# MOSEFET_CONTROLLER_V8.net
KiCad netlist of a schematic drawn in EAGLE
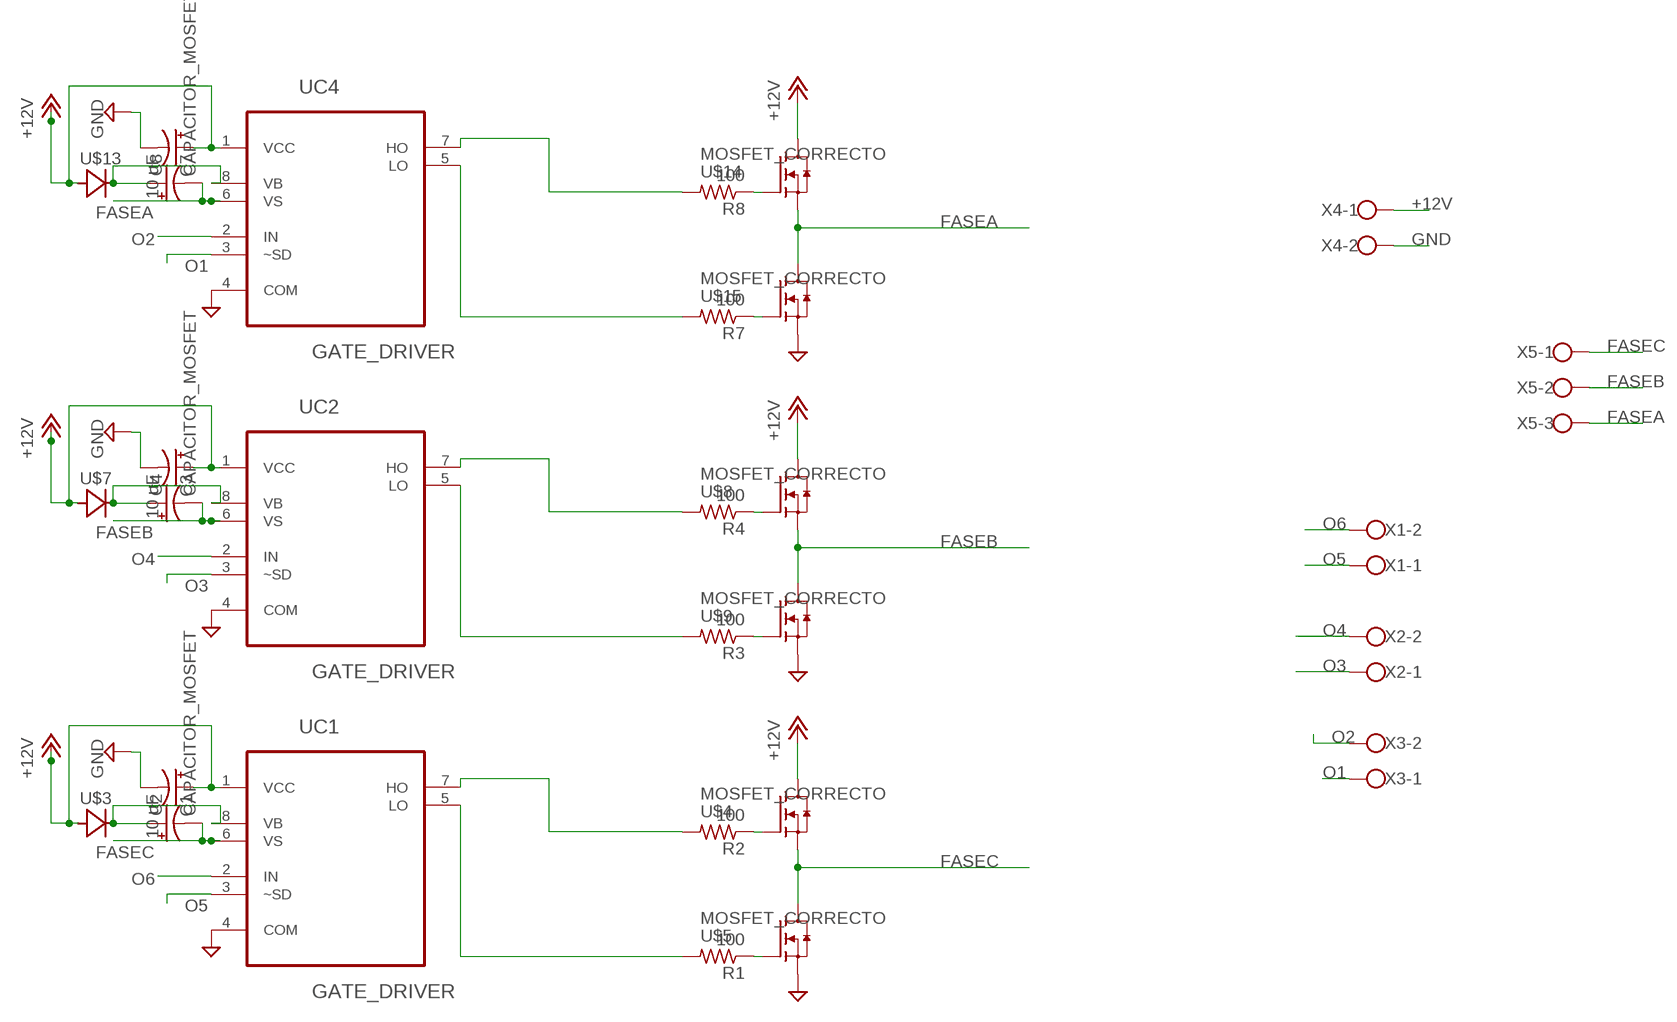
[diagram p0: schematic, sheet 1]

(export (version "E")
  (design (tool "Eeschema 10.0.6"))
  (components
    (comp (ref "C1")
      (value "10 uF")
      (footprint "eagle-import:153CLV-0505")
      (libsource (lib "eagle-import") (part "CAP_SMD"))
    )
    (comp (ref "C2")
      (value "CAPACITOR_MOSFET")
      (footprint "eagle-import:E2,5-5")
      (libsource (lib "eagle-import") (part "CAPACITOR_MOSFET"))
    )
    (comp (ref "C3")
      (value "10 uF")
      (footprint "eagle-import:153CLV-0505")
      (libsource (lib "eagle-import") (part "CAP_SMD"))
    )
    (comp (ref "C4")
      (value "CAPACITOR_MOSFET")
      (footprint "eagle-import:E2,5-5")
      (libsource (lib "eagle-import") (part "CAPACITOR_MOSFET"))
    )
    (comp (ref "C7")
      (value "10 uF")
      (footprint "eagle-import:153CLV-0505")
      (libsource (lib "eagle-import") (part "CAP_SMD"))
    )
    (comp (ref "C8")
      (value "CAPACITOR_MOSFET")
      (footprint "eagle-import:E2,5-5")
      (libsource (lib "eagle-import") (part "CAPACITOR_MOSFET"))
    )
    (comp (ref "R1")
      (value "100")
      (footprint "eagle-import:R1206")
      (libsource (lib "eagle-import") (part "R-US_R1206"))
    )
    (comp (ref "R2")
      (value "100")
      (footprint "eagle-import:R1206")
      (libsource (lib "eagle-import") (part "R-US_R1206"))
    )
    (comp (ref "R3")
      (value "100")
      (footprint "eagle-import:R1206")
      (libsource (lib "eagle-import") (part "R-US_R1206"))
    )
    (comp (ref "R4")
      (value "100")
      (footprint "eagle-import:R1206")
      (libsource (lib "eagle-import") (part "R-US_R1206"))
    )
    (comp (ref "R7")
      (value "100")
      (footprint "eagle-import:R1206")
      (libsource (lib "eagle-import") (part "R-US_R1206"))
    )
    (comp (ref "R8")
      (value "100")
      (footprint "eagle-import:R1206")
      (libsource (lib "eagle-import") (part "R-US_R1206"))
    )
    (comp (ref "U$3")
      (value "DIODO_SMD")
      (footprint "eagle-import:DO214AC")
      (libsource (lib "eagle-import") (part "DIODO_SMD"))
    )
    (comp (ref "U$4")
      (value "MOSFET_CORRECTO")
      (footprint "eagle-import:MOSFET_BUENO")
      (libsource (lib "eagle-import") (part "MOSFET_CORRECTO"))
    )
    (comp (ref "U$5")
      (value "MOSFET_CORRECTO")
      (footprint "eagle-import:MOSFET_BUENO")
      (libsource (lib "eagle-import") (part "MOSFET_CORRECTO"))
    )
    (comp (ref "U$7")
      (value "DIODO_SMD")
      (footprint "eagle-import:DO214AC")
      (libsource (lib "eagle-import") (part "DIODO_SMD"))
    )
    (comp (ref "U$8")
      (value "MOSFET_CORRECTO")
      (footprint "eagle-import:MOSFET_BUENO")
      (libsource (lib "eagle-import") (part "MOSFET_CORRECTO"))
    )
    (comp (ref "U$9")
      (value "MOSFET_CORRECTO")
      (footprint "eagle-import:MOSFET_BUENO")
      (libsource (lib "eagle-import") (part "MOSFET_CORRECTO"))
    )
    (comp (ref "U$13")
      (value "DIODO_SMD")
      (footprint "eagle-import:DO214AC")
      (libsource (lib "eagle-import") (part "DIODO_SMD"))
    )
    (comp (ref "U$14")
      (value "MOSFET_CORRECTO")
      (footprint "eagle-import:MOSFET_BUENO")
      (libsource (lib "eagle-import") (part "MOSFET_CORRECTO"))
    )
    (comp (ref "U$15")
      (value "MOSFET_CORRECTO")
      (footprint "eagle-import:MOSFET_BUENO")
      (libsource (lib "eagle-import") (part "MOSFET_CORRECTO"))
    )
    (comp (ref "UC1")
      (value "GATE_DRIVER")
      (footprint "eagle-import:GATE_DRIVER")
      (libsource (lib "eagle-import") (part "GATE_DRIVER"))
    )
    (comp (ref "UC2")
      (value "GATE_DRIVER")
      (footprint "eagle-import:GATE_DRIVER")
      (libsource (lib "eagle-import") (part "GATE_DRIVER"))
    )
    (comp (ref "UC4")
      (value "GATE_DRIVER")
      (footprint "eagle-import:GATE_DRIVER")
      (libsource (lib "eagle-import") (part "GATE_DRIVER"))
    )
    (comp (ref "X1")
      (value "W237-102")
      (footprint "eagle-import:W237-102")
      (fields (field (name "MPN") "237-102"))
      (libsource (lib "eagle-import") (part "W237-102"))
    )
    (comp (ref "X2")
      (value "W237-102")
      (footprint "eagle-import:W237-102")
      (fields (field (name "MPN") "237-102"))
      (libsource (lib "eagle-import") (part "W237-102"))
    )
    (comp (ref "X3")
      (value "W237-102")
      (footprint "eagle-import:W237-102")
      (fields (field (name "MPN") "237-102"))
      (libsource (lib "eagle-import") (part "W237-102"))
    )
    (comp (ref "X4")
      (value "W237-102")
      (footprint "eagle-import:W237-102")
      (fields (field (name "MPN") "237-102"))
      (libsource (lib "eagle-import") (part "W237-102"))
    )
    (comp (ref "X5")
      (value "W237-103")
      (footprint "eagle-import:W237-103")
      (fields (field (name "MPN") "237-103"))
      (libsource (lib "eagle-import") (part "W237-103"))
    )
  )
  (nets
    (net (code "1") (name "+12V") (class "Default")
      (node (ref "C1") (pin "+") (pinfunction "+_+") (pintype "passive"))
      (node (ref "C3") (pin "+") (pinfunction "+_+") (pintype "passive"))
      (node (ref "C7") (pin "+") (pinfunction "+_+") (pintype "passive"))
      (node (ref "U$13") (pin "A") (pinfunction "A_A") (pintype "passive"))
      (node (ref "U$14") (pin "3") (pinfunction "D_3") (pintype "passive"))
      (node (ref "U$3") (pin "A") (pinfunction "A_A") (pintype "passive"))
      (node (ref "U$4") (pin "3") (pinfunction "D_3") (pintype "passive"))
      (node (ref "U$7") (pin "A") (pinfunction "A_A") (pintype "passive"))
      (node (ref "U$8") (pin "3") (pinfunction "D_3") (pintype "passive"))
      (node (ref "UC1") (pin "1") (pinfunction "VCC_1") (pintype "power_in"))
      (node (ref "UC2") (pin "1") (pinfunction "VCC_1") (pintype "power_in"))
      (node (ref "UC4") (pin "1") (pinfunction "VCC_1") (pintype "power_in"))
      (node (ref "X4") (pin "1") (pinfunction "KL_1") (pintype "passive"))
    )
    (net (code "2") (name "/FASEA") (class "Default")
      (node (ref "C8") (pin "-") (pinfunction "-_-") (pintype "passive"))
      (node (ref "U$14") (pin "2") (pinfunction "S_2") (pintype "passive"))
      (node (ref "U$15") (pin "3") (pinfunction "D_3") (pintype "passive"))
      (node (ref "UC4") (pin "6") (pinfunction "VS_6") (pintype "power_in"))
      (node (ref "X5") (pin "3") (pinfunction "KL_3") (pintype "passive"))
    )
    (net (code "3") (name "/FASEB") (class "Default")
      (node (ref "C4") (pin "-") (pinfunction "-_-") (pintype "passive"))
      (node (ref "U$8") (pin "2") (pinfunction "S_2") (pintype "passive"))
      (node (ref "U$9") (pin "3") (pinfunction "D_3") (pintype "passive"))
      (node (ref "UC2") (pin "6") (pinfunction "VS_6") (pintype "power_in"))
      (node (ref "X5") (pin "2") (pinfunction "KL_2") (pintype "passive"))
    )
    (net (code "4") (name "/FASEC") (class "Default")
      (node (ref "C2") (pin "-") (pinfunction "-_-") (pintype "passive"))
      (node (ref "U$4") (pin "2") (pinfunction "S_2") (pintype "passive"))
      (node (ref "U$5") (pin "3") (pinfunction "D_3") (pintype "passive"))
      (node (ref "UC1") (pin "6") (pinfunction "VS_6") (pintype "power_in"))
      (node (ref "X5") (pin "1") (pinfunction "KL_1") (pintype "passive"))
    )
    (net (code "5") (name "/O1") (class "Default")
      (node (ref "UC4") (pin "3") (pinfunction "~{SD}_3") (pintype "input"))
      (node (ref "X3") (pin "1") (pinfunction "KL_1") (pintype "passive"))
    )
    (net (code "6") (name "/O2") (class "Default")
      (node (ref "UC4") (pin "2") (pinfunction "IN_2") (pintype "input"))
      (node (ref "X3") (pin "2") (pinfunction "KL_2") (pintype "passive"))
    )
    (net (code "7") (name "/O3") (class "Default")
      (node (ref "UC2") (pin "3") (pinfunction "~{SD}_3") (pintype "input"))
      (node (ref "X2") (pin "1") (pinfunction "KL_1") (pintype "passive"))
    )
    (net (code "8") (name "/O4") (class "Default")
      (node (ref "UC2") (pin "2") (pinfunction "IN_2") (pintype "input"))
      (node (ref "X2") (pin "2") (pinfunction "KL_2") (pintype "passive"))
    )
    (net (code "9") (name "/O5") (class "Default")
      (node (ref "UC1") (pin "3") (pinfunction "~{SD}_3") (pintype "input"))
      (node (ref "X1") (pin "1") (pinfunction "KL_1") (pintype "passive"))
    )
    (net (code "10") (name "/O6") (class "Default")
      (node (ref "UC1") (pin "2") (pinfunction "IN_2") (pintype "input"))
      (node (ref "X1") (pin "2") (pinfunction "KL_2") (pintype "passive"))
    )
    (net (code "11") (name "GND") (class "Default")
      (node (ref "C1") (pin "-") (pinfunction "-_-") (pintype "passive"))
      (node (ref "C3") (pin "-") (pinfunction "-_-") (pintype "passive"))
      (node (ref "C7") (pin "-") (pinfunction "-_-") (pintype "passive"))
      (node (ref "U$15") (pin "2") (pinfunction "S_2") (pintype "passive"))
      (node (ref "U$5") (pin "2") (pinfunction "S_2") (pintype "passive"))
      (node (ref "U$9") (pin "2") (pinfunction "S_2") (pintype "passive"))
      (node (ref "UC1") (pin "4") (pinfunction "COM_4") (pintype "input"))
      (node (ref "UC2") (pin "4") (pinfunction "COM_4") (pintype "input"))
      (node (ref "UC4") (pin "4") (pinfunction "COM_4") (pintype "input"))
      (node (ref "X4") (pin "2") (pinfunction "KL_2") (pintype "passive"))
    )
    (net (code "12") (name "Net-(U$4-G)") (class "Default")
      (node (ref "R2") (pin "1") (pinfunction "1_1") (pintype "passive"))
      (node (ref "U$4") (pin "1") (pinfunction "G_1") (pintype "passive"))
    )
    (net (code "13") (name "Net-(U$5-G)") (class "Default")
      (node (ref "R1") (pin "1") (pinfunction "1_1") (pintype "passive"))
      (node (ref "U$5") (pin "1") (pinfunction "G_1") (pintype "passive"))
    )
    (net (code "14") (name "Net-(U$8-G)") (class "Default")
      (node (ref "R4") (pin "1") (pinfunction "1_1") (pintype "passive"))
      (node (ref "U$8") (pin "1") (pinfunction "G_1") (pintype "passive"))
    )
    (net (code "15") (name "Net-(U$9-G)") (class "Default")
      (node (ref "R3") (pin "1") (pinfunction "1_1") (pintype "passive"))
      (node (ref "U$9") (pin "1") (pinfunction "G_1") (pintype "passive"))
    )
    (net (code "16") (name "Net-(U$14-G)") (class "Default")
      (node (ref "R8") (pin "1") (pinfunction "1_1") (pintype "passive"))
      (node (ref "U$14") (pin "1") (pinfunction "G_1") (pintype "passive"))
    )
    (net (code "17") (name "Net-(U$15-G)") (class "Default")
      (node (ref "R7") (pin "1") (pinfunction "1_1") (pintype "passive"))
      (node (ref "U$15") (pin "1") (pinfunction "G_1") (pintype "passive"))
    )
    (net (code "18") (name "Net-(UC1-HO)") (class "Default")
      (node (ref "R2") (pin "2") (pinfunction "2_2") (pintype "passive"))
      (node (ref "UC1") (pin "7") (pinfunction "HO_7") (pintype "output"))
    )
    (net (code "19") (name "Net-(UC1-LO)") (class "Default")
      (node (ref "R1") (pin "2") (pinfunction "2_2") (pintype "passive"))
      (node (ref "UC1") (pin "5") (pinfunction "LO_5") (pintype "output"))
    )
    (net (code "20") (name "Net-(UC1-VB)") (class "Default")
      (node (ref "C2") (pin "+") (pinfunction "+_+") (pintype "passive"))
      (node (ref "U$3") (pin "C") (pinfunction "C_C") (pintype "passive"))
      (node (ref "UC1") (pin "8") (pinfunction "VB_8") (pintype "power_in"))
    )
    (net (code "21") (name "Net-(UC2-HO)") (class "Default")
      (node (ref "R4") (pin "2") (pinfunction "2_2") (pintype "passive"))
      (node (ref "UC2") (pin "7") (pinfunction "HO_7") (pintype "output"))
    )
    (net (code "22") (name "Net-(UC2-LO)") (class "Default")
      (node (ref "R3") (pin "2") (pinfunction "2_2") (pintype "passive"))
      (node (ref "UC2") (pin "5") (pinfunction "LO_5") (pintype "output"))
    )
    (net (code "23") (name "Net-(UC2-VB)") (class "Default")
      (node (ref "C4") (pin "+") (pinfunction "+_+") (pintype "passive"))
      (node (ref "U$7") (pin "C") (pinfunction "C_C") (pintype "passive"))
      (node (ref "UC2") (pin "8") (pinfunction "VB_8") (pintype "power_in"))
    )
    (net (code "24") (name "Net-(UC4-HO)") (class "Default")
      (node (ref "R8") (pin "2") (pinfunction "2_2") (pintype "passive"))
      (node (ref "UC4") (pin "7") (pinfunction "HO_7") (pintype "output"))
    )
    (net (code "25") (name "Net-(UC4-LO)") (class "Default")
      (node (ref "R7") (pin "2") (pinfunction "2_2") (pintype "passive"))
      (node (ref "UC4") (pin "5") (pinfunction "LO_5") (pintype "output"))
    )
    (net (code "26") (name "Net-(UC4-VB)") (class "Default")
      (node (ref "C8") (pin "+") (pinfunction "+_+") (pintype "passive"))
      (node (ref "U$13") (pin "C") (pinfunction "C_C") (pintype "passive"))
      (node (ref "UC4") (pin "8") (pinfunction "VB_8") (pintype "power_in"))
    )
  )
)
